# m2_feather_interposer.net
KiCad netlist of a schematic drawn in EAGLE
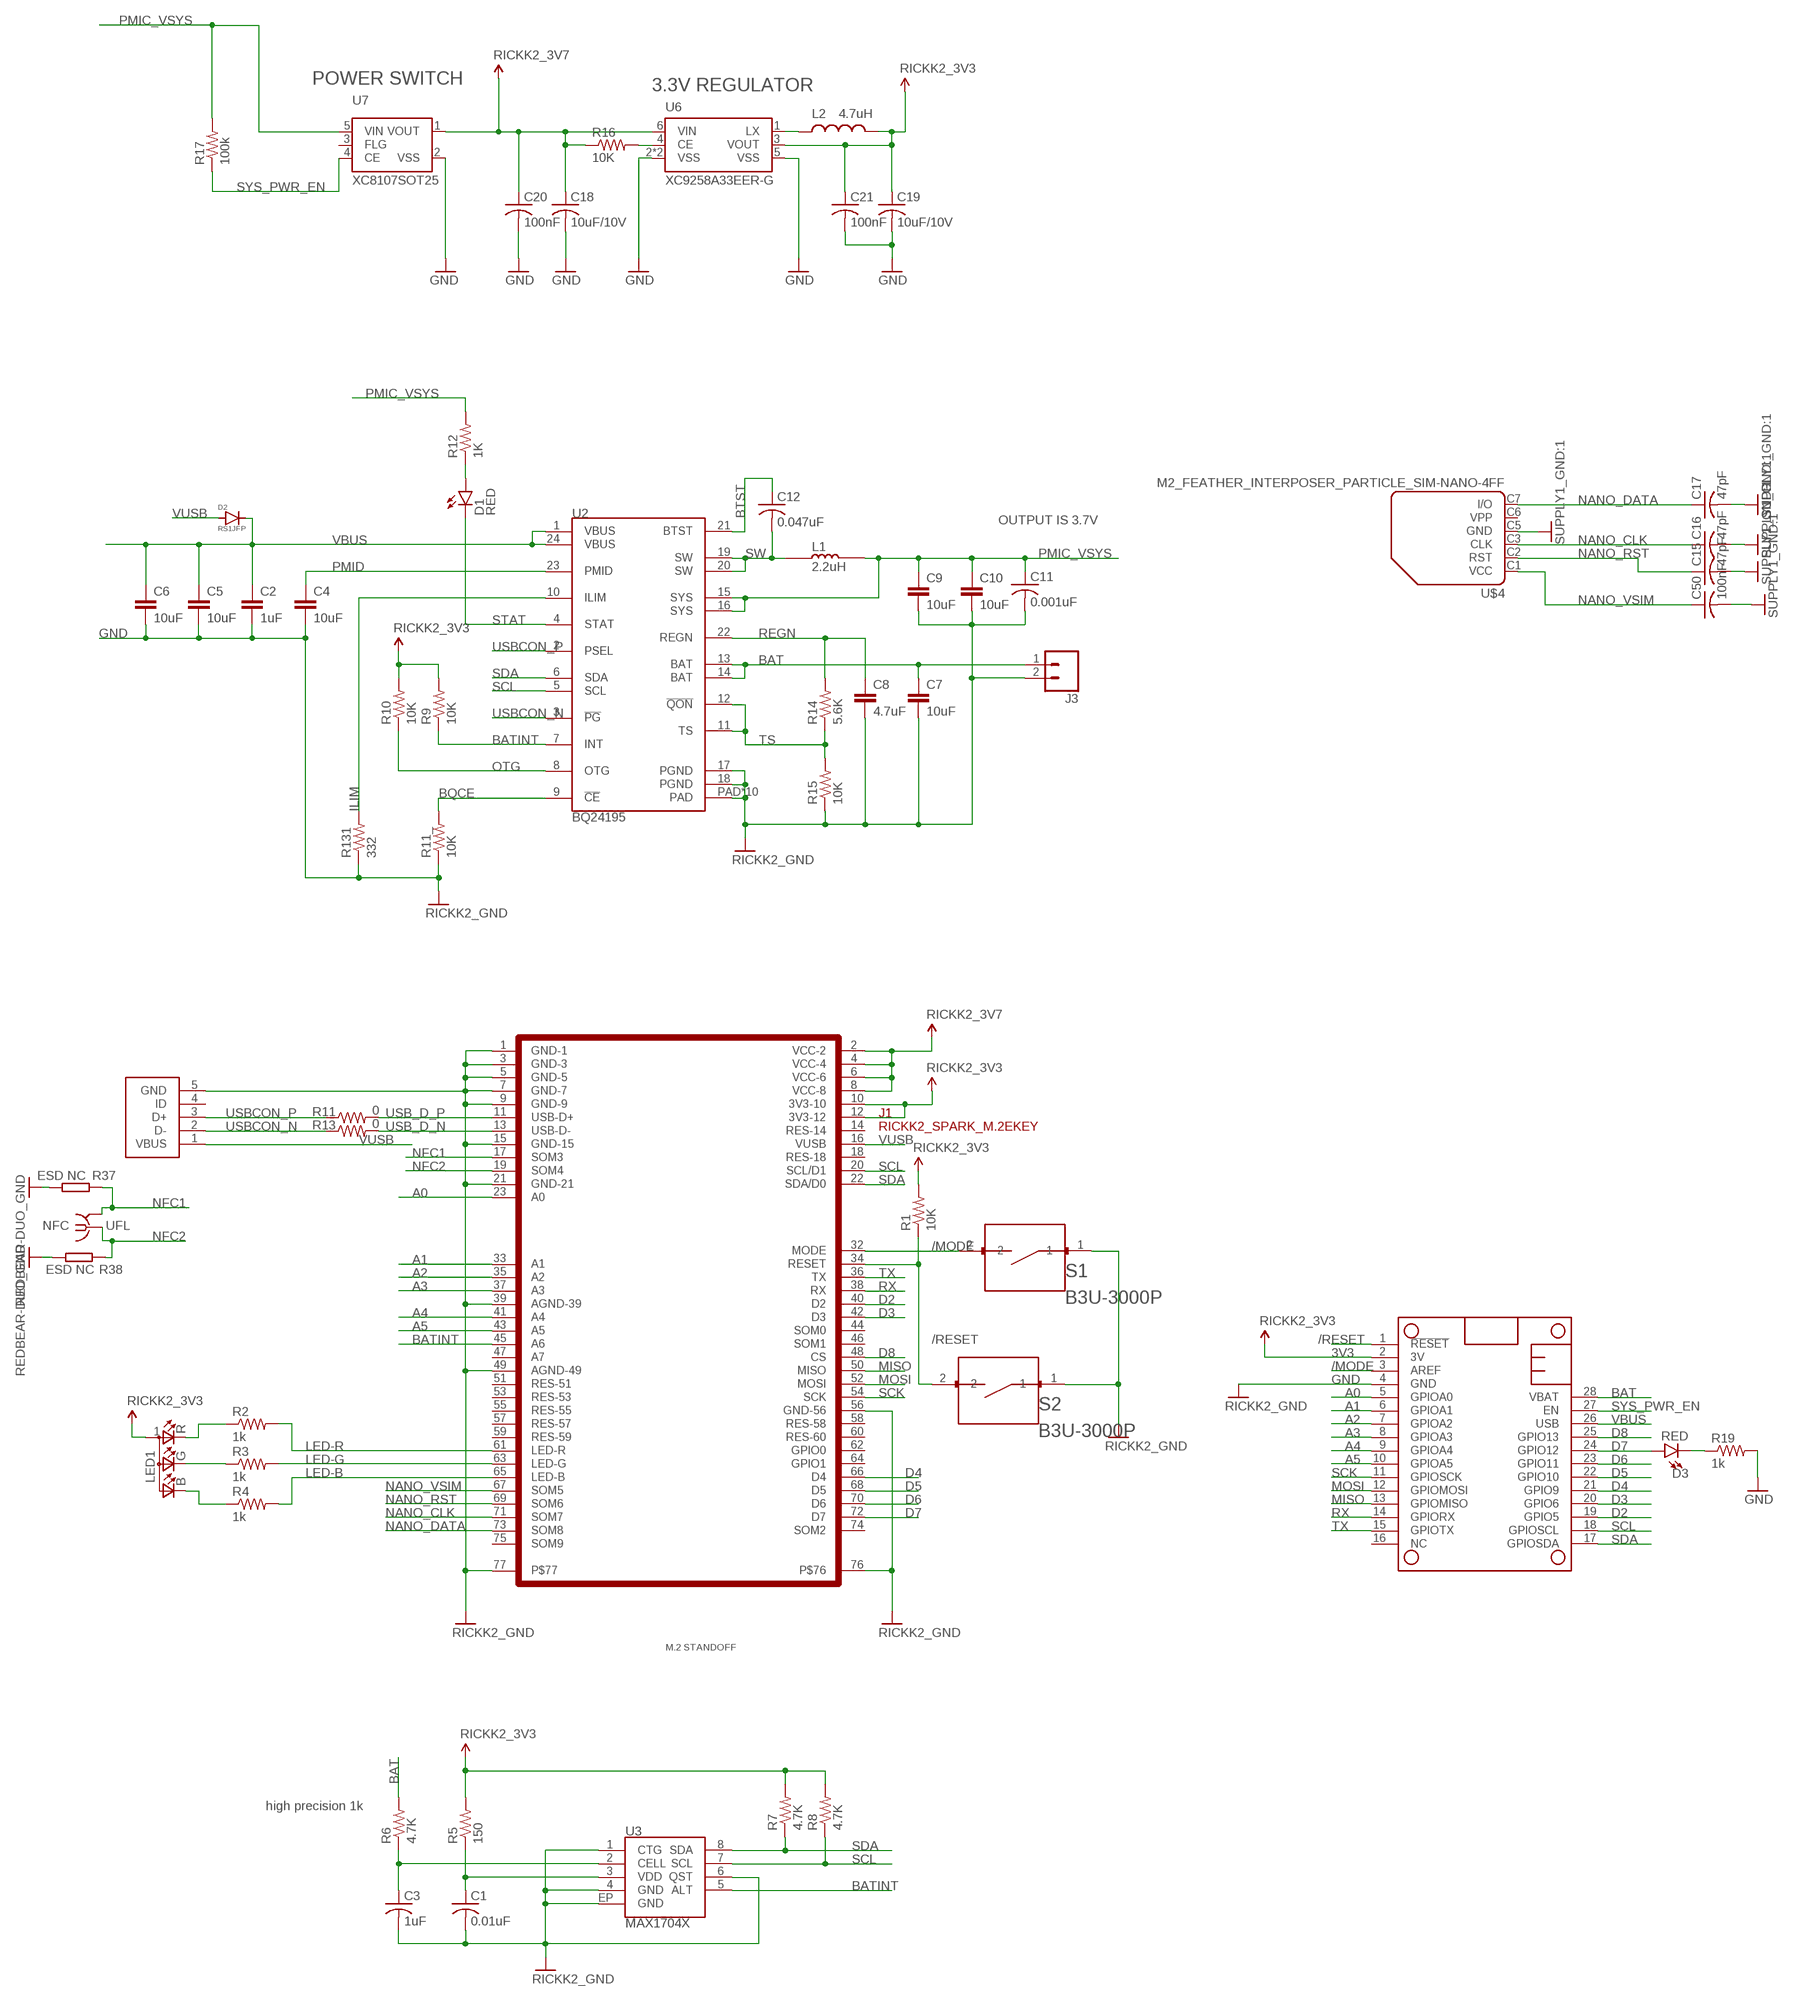
[diagram p0: schematic, sheet 1]

(export (version "E")
  (design (tool "Eeschema 10.0.6"))
  (components
    (comp (ref "C1")
      (value "0.01uF")
      (footprint "eagle-import:C0402")
      (libsource (lib "eagle-import") (part "C-USC0402"))
    )
    (comp (ref "C2")
      (value "1uF")
      (footprint "eagle-import:0603-CAP")
      (libsource (lib "eagle-import") (part "CAP-1UF-0603.DEV"))
    )
    (comp (ref "C3")
      (value "1uF")
      (footprint "eagle-import:C0402")
      (libsource (lib "eagle-import") (part "C-USC0402"))
    )
    (comp (ref "C4")
      (value "10uF")
      (footprint "eagle-import:RICKK2_0603-CAP")
      (libsource (lib "eagle-import") (part "RICKK2_CAP-10UF-0603"))
    )
    (comp (ref "C5")
      (value "10uF")
      (footprint "eagle-import:RICKK2_0603-CAP")
      (libsource (lib "eagle-import") (part "RICKK2_CAP-10UF-0603"))
    )
    (comp (ref "C6")
      (value "10uF")
      (footprint "eagle-import:RICKK2_0603-CAP")
      (libsource (lib "eagle-import") (part "RICKK2_CAP-10UF-0603"))
    )
    (comp (ref "C7")
      (value "10uF")
      (footprint "eagle-import:RICKK2_0603-CAP")
      (libsource (lib "eagle-import") (part "RICKK2_CAP-10UF-0603"))
    )
    (comp (ref "C8")
      (value "4.7uF")
      (footprint "eagle-import:RICKK2_0603-CAP")
      (libsource (lib "eagle-import") (part "RICKK2_CAP-4.7UF-0603"))
    )
    (comp (ref "C9")
      (value "10uF")
      (footprint "eagle-import:RICKK2_0603-CAP")
      (libsource (lib "eagle-import") (part "RICKK2_CAP-10UF-0603"))
    )
    (comp (ref "C10")
      (value "10uF")
      (footprint "eagle-import:RICKK2_0603-CAP")
      (libsource (lib "eagle-import") (part "RICKK2_CAP-10UF-0603"))
    )
    (comp (ref "C11")
      (value "0.001uF")
      (footprint "eagle-import:C0402")
      (libsource (lib "eagle-import") (part "C-USC0402"))
    )
    (comp (ref "C12")
      (value "0.047uF")
      (footprint "eagle-import:C0402")
      (libsource (lib "eagle-import") (part "C-USC0402"))
    )
    (comp (ref "C15")
      (value "47pF")
      (footprint "eagle-import:PARTICLE_C0201_B")
      (libsource (lib "eagle-import") (part "PARTICLE_C-USC0201_B"))
    )
    (comp (ref "C16")
      (value "47pF")
      (footprint "eagle-import:PARTICLE_C0201_B")
      (libsource (lib "eagle-import") (part "PARTICLE_C-USC0201_B"))
    )
    (comp (ref "C17")
      (value "47pF")
      (footprint "eagle-import:PARTICLE_C0201_B")
      (libsource (lib "eagle-import") (part "PARTICLE_C-USC0201_B"))
    )
    (comp (ref "C18")
      (value "10uF/10V")
      (footprint "eagle-import:C0603K")
      (libsource (lib "eagle-import") (part "rcl_334_C-USC0603K"))
    )
    (comp (ref "C19")
      (value "10uF/10V")
      (footprint "eagle-import:C0603K")
      (libsource (lib "eagle-import") (part "rcl_334_C-USC0603K"))
    )
    (comp (ref "C20")
      (value "100nF")
      (footprint "eagle-import:C0603K")
      (libsource (lib "eagle-import") (part "rcl_334_C-USC0603K"))
    )
    (comp (ref "C21")
      (value "100nF")
      (footprint "eagle-import:C0201_B")
      (libsource (lib "eagle-import") (part "C-USC0201_B"))
    )
    (comp (ref "C50")
      (value "100nF")
      (footprint "eagle-import:PARTICLE_C0201_B")
      (libsource (lib "eagle-import") (part "PARTICLE_C-USC0201_B"))
    )
    (comp (ref "D1")
      (value "RED")
      (footprint "eagle-import:RICKK2_LED-0603")
      (libsource (lib "eagle-import") (part "RICKK2_LED-RED"))
    )
    (comp (ref "D2")
      (value "RS1JFP")
      (footprint "eagle-import:RICKK2_SOD-123HE-ON")
      (libsource (lib "eagle-import") (part "RICKK2_DIODE-RS1JFP"))
    )
    (comp (ref "D3")
      (value "RED")
      (footprint "eagle-import:LED-0603")
      (libsource (lib "eagle-import") (part "LED-RED0603"))
    )
    (comp (ref "J1")
      (value "RICKK2_SPARK_M.2EKEY")
      (footprint "eagle-import:RICKK2_SPARK_M.2EKEY-LESS-CREAM")
      (libsource (lib "eagle-import") (part "RICKK2_SPARK_M.2EKEY"))
    )
    (comp (ref "J3")
      (value "CONN_02")
      (footprint "eagle-import:1X02")
      (libsource (lib "eagle-import") (part "CONN_02"))
    )
    (comp (ref "L1")
      (value "2.2uH")
      (footprint "eagle-import:RICKK2_1008-BOURNS")
      (libsource (lib "eagle-import") (part "RICKK2_INDUCTOR-2.2UH"))
    )
    (comp (ref "L2")
      (value "4.7uH")
      (footprint "eagle-import:INDUCTOR-VLS-E")
      (libsource (lib "eagle-import") (part "INDUCTOR-SPARKFUNVLS3012ET-4R7M"))
    )
    (comp (ref "LED1")
      (value "RICKK2_LED-RGB-CREE-SMD")
      (footprint "eagle-import:RICKK2_LED-RGB-CREE-SMD")
      (libsource (lib "eagle-import") (part "RICKK2_LED-RGB-CREE-SMD"))
    )
    (comp (ref "MS1")
      (value "MICROBUILDER_FEATHERWINGSMT_BTM_FEATHER")
      (footprint "eagle-import:SMT_BTM_FEATHERWING")
      (libsource (lib "eagle-import") (part "MICROBUILDER_FEATHERWINGSMT_BTM_FEATHER"))
    )
    (comp (ref "NFC")
      (value "UFL")
      (footprint "eagle-import:PARTICLE_IPEX-20279-001E")
      (libsource (lib "eagle-import") (part "PARTICLE_IPEX-20279-001E"))
    )
    (comp (ref "R1")
      (value "10K")
      (footprint "eagle-import:R0402")
      (libsource (lib "eagle-import") (part "R-US_R0402"))
    )
    (comp (ref "R2")
      (value "1k")
      (footprint "eagle-import:R0402")
      (libsource (lib "eagle-import") (part "R-US_R0402"))
    )
    (comp (ref "R3")
      (value "1k")
      (footprint "eagle-import:R0402")
      (libsource (lib "eagle-import") (part "R-US_R0402"))
    )
    (comp (ref "R4")
      (value "1k")
      (footprint "eagle-import:R0402")
      (libsource (lib "eagle-import") (part "R-US_R0402"))
    )
    (comp (ref "R5")
      (value "150")
      (footprint "eagle-import:R0402")
      (libsource (lib "eagle-import") (part "R-US_R0402"))
    )
    (comp (ref "R6")
      (value "4.7K")
      (footprint "eagle-import:R0402")
      (libsource (lib "eagle-import") (part "R-US_R0402"))
    )
    (comp (ref "R7")
      (value "4.7K")
      (footprint "eagle-import:R0402")
      (libsource (lib "eagle-import") (part "R-US_R0402"))
    )
    (comp (ref "R8")
      (value "4.7K")
      (footprint "eagle-import:R0402")
      (libsource (lib "eagle-import") (part "R-US_R0402"))
    )
    (comp (ref "R9")
      (value "10K")
      (footprint "eagle-import:R0402")
      (libsource (lib "eagle-import") (part "R-US_R0402"))
    )
    (comp (ref "R10")
      (value "10K")
      (footprint "eagle-import:R0402")
      (libsource (lib "eagle-import") (part "R-US_R0402"))
    )
    (comp (ref "R11")
      (value "0")
      (footprint "eagle-import:R0402")
      (libsource (lib "eagle-import") (part "R-US_R0402"))
    )
    (comp (ref "R11_")
      (value "10K")
      (footprint "eagle-import:R0402")
      (libsource (lib "eagle-import") (part "R-US_R0402"))
    )
    (comp (ref "R12")
      (value "1K")
      (footprint "eagle-import:R0402")
      (libsource (lib "eagle-import") (part "R-US_R0402"))
    )
    (comp (ref "R13")
      (value "0")
      (footprint "eagle-import:R0402")
      (libsource (lib "eagle-import") (part "R-US_R0402"))
    )
    (comp (ref "R14")
      (value "5.6K")
      (footprint "eagle-import:R0402")
      (libsource (lib "eagle-import") (part "R-US_R0402"))
    )
    (comp (ref "R15")
      (value "10K")
      (footprint "eagle-import:R0402")
      (libsource (lib "eagle-import") (part "R-US_R0402"))
    )
    (comp (ref "R16")
      (value "10K")
      (footprint "eagle-import:R0402")
      (libsource (lib "eagle-import") (part "R-US_R0402"))
    )
    (comp (ref "R17")
      (value "100k")
      (footprint "eagle-import:R0402")
      (libsource (lib "eagle-import") (part "R-US_R0402"))
    )
    (comp (ref "R19")
      (value "1k")
      (footprint "eagle-import:R0402")
      (libsource (lib "eagle-import") (part "R-US_R0402"))
    )
    (comp (ref "R37")
      (value "ESD NC")
      (footprint "eagle-import:REDBEAR_R-0402S")
      (libsource (lib "eagle-import") (part "REDBEAR_RES0402S"))
    )
    (comp (ref "R38")
      (value "ESD NC")
      (footprint "eagle-import:REDBEAR_R-0402S")
      (libsource (lib "eagle-import") (part "REDBEAR_RES0402S"))
    )
    (comp (ref "R131")
      (value "332")
      (footprint "eagle-import:R0402")
      (libsource (lib "eagle-import") (part "R-US_R0402"))
    )
    (comp (ref "S1")
      (value "B3U-3000P")
      (footprint "eagle-import:SW_B3U-3000P")
      (fields (field (name "MF") "Omron") (field (name "MP") "B3U-3100P-B"))
      (libsource (lib "eagle-import") (part "B3U-3000P"))
    )
    (comp (ref "S2")
      (value "B3U-3000P")
      (footprint "eagle-import:SW_B3U-3000P")
      (fields (field (name "MF") "Omron") (field (name "MP") "B3U-3100P-B"))
      (libsource (lib "eagle-import") (part "B3U-3000P"))
    )
    (comp (ref "U$1")
      (value "RICKK2_M2-STANDOFF")
      (footprint "eagle-import:RICKK2_M2-STANDOFF")
      (libsource (lib "eagle-import") (part "RICKK2_M2-STANDOFF"))
    )
    (comp (ref "U$3")
      (value "RICKK2_USB-MICRO-B-SOCKET-AMPHENOL")
      (footprint "eagle-import:RICKK2_USB-B-SMT-AMPHENOL")
      (libsource (lib "eagle-import") (part "RICKK2_USB-MICRO-B-SOCKET-AMPHENOL"))
    )
    (comp (ref "U$4")
      (value "M2_FEATHER_INTERPOSER_PARTICLE_SIM-NANO-4FF")
      (footprint "eagle-import:M2_FEATHER_INTERPOSER_PARTICLE_GCT-SIM8100")
      (libsource (lib "eagle-import") (part "M2_FEATHER_INTERPOSER_PARTICLE_SIM-NANO-4FF"))
    )
    (comp (ref "U2")
      (value "BQ24195")
      (footprint "eagle-import:RICKK2_24VFQN-TI")
      (libsource (lib "eagle-import") (part "RICKK2_BQ24195"))
    )
    (comp (ref "U3")
      (value "MAX1704X")
      (footprint "eagle-import:TDFN-8")
      (libsource (lib "eagle-import") (part "MAX1704X"))
    )
    (comp (ref "U6")
      (value "XC9258A33EER-G")
      (footprint "eagle-import:USP-6C")
      (libsource (lib "eagle-import") (part "XC9258A33EER-G"))
    )
    (comp (ref "U7")
      (value "XC8107SOT25")
      (footprint "eagle-import:SOT25")
      (libsource (lib "eagle-import") (part "XC8107SOT25"))
    )
  )
  (nets
    (net (code "1") (name "/A0") (class "Default")
      (node (ref "J1") (pin "23") (pinfunction "A0_23") (pintype "bidirectional"))
      (node (ref "MS1") (pin "5") (pinfunction "GPIOA0_5") (pintype "bidirectional"))
    )
    (net (code "2") (name "/A1") (class "Default")
      (node (ref "J1") (pin "33") (pinfunction "A1_33") (pintype "bidirectional"))
      (node (ref "MS1") (pin "6") (pinfunction "GPIOA1_6") (pintype "bidirectional"))
    )
    (net (code "3") (name "/A2") (class "Default")
      (node (ref "J1") (pin "35") (pinfunction "A2_35") (pintype "bidirectional"))
      (node (ref "MS1") (pin "7") (pinfunction "GPIOA2_7") (pintype "bidirectional"))
    )
    (net (code "4") (name "/A3") (class "Default")
      (node (ref "J1") (pin "37") (pinfunction "A3_37") (pintype "bidirectional"))
      (node (ref "MS1") (pin "8") (pinfunction "GPIOA3_8") (pintype "bidirectional"))
    )
    (net (code "5") (name "/A4") (class "Default")
      (node (ref "J1") (pin "41") (pinfunction "A4_41") (pintype "bidirectional"))
      (node (ref "MS1") (pin "9") (pinfunction "GPIOA4_9") (pintype "bidirectional"))
    )
    (net (code "6") (name "/A5") (class "Default")
      (node (ref "J1") (pin "43") (pinfunction "A5_43") (pintype "bidirectional"))
      (node (ref "MS1") (pin "10") (pinfunction "GPIOA5_10") (pintype "bidirectional"))
    )
    (net (code "7") (name "/BAT") (class "Default")
      (node (ref "C7") (pin "1") (pinfunction "1_1") (pintype "passive"))
      (node (ref "J3") (pin "1") (pinfunction "1_1") (pintype "passive"))
      (node (ref "MS1") (pin "28") (pinfunction "VBAT_28") (pintype "power_in"))
      (node (ref "R6") (pin "2") (pinfunction "2_2") (pintype "passive"))
      (node (ref "U2") (pin "13") (pinfunction "BAT_13") (pintype "passive"))
      (node (ref "U2") (pin "14") (pinfunction "BAT_14") (pintype "power_in"))
    )
    (net (code "8") (name "/BATINT") (class "Default")
      (node (ref "J1") (pin "45") (pinfunction "A6_45") (pintype "bidirectional"))
      (node (ref "R9") (pin "1") (pinfunction "1_1") (pintype "passive"))
      (node (ref "U2") (pin "7") (pinfunction "INT_7") (pintype "bidirectional"))
      (node (ref "U3") (pin "5") (pinfunction "ALT_5") (pintype "bidirectional"))
    )
    (net (code "9") (name "/BQCE") (class "Default")
      (node (ref "R11_") (pin "2") (pinfunction "2_2") (pintype "passive"))
      (node (ref "U2") (pin "9") (pinfunction "~{CE}_9") (pintype "output"))
    )
    (net (code "10") (name "/BTST") (class "Default")
      (node (ref "C12") (pin "1") (pinfunction "1_1") (pintype "passive"))
      (node (ref "U2") (pin "21") (pinfunction "BTST_21") (pintype "bidirectional"))
    )
    (net (code "11") (name "/D2") (class "Default")
      (node (ref "J1") (pin "40") (pinfunction "D2_40") (pintype "bidirectional"))
      (node (ref "MS1") (pin "19") (pinfunction "GPIO5_19") (pintype "bidirectional"))
    )
    (net (code "12") (name "/D3") (class "Default")
      (node (ref "J1") (pin "42") (pinfunction "D3_42") (pintype "bidirectional"))
      (node (ref "MS1") (pin "20") (pinfunction "GPIO6_20") (pintype "bidirectional"))
    )
    (net (code "13") (name "/D4") (class "Default")
      (node (ref "J1") (pin "66") (pinfunction "D4_66") (pintype "bidirectional"))
      (node (ref "MS1") (pin "21") (pinfunction "GPIO9_21") (pintype "bidirectional"))
    )
    (net (code "14") (name "/D5") (class "Default")
      (node (ref "J1") (pin "68") (pinfunction "D5_68") (pintype "bidirectional"))
      (node (ref "MS1") (pin "22") (pinfunction "GPIO10_22") (pintype "bidirectional"))
    )
    (net (code "15") (name "/D6") (class "Default")
      (node (ref "J1") (pin "70") (pinfunction "D6_70") (pintype "bidirectional"))
      (node (ref "MS1") (pin "23") (pinfunction "GPIO11_23") (pintype "bidirectional"))
    )
    (net (code "16") (name "/D7") (class "Default")
      (node (ref "D3") (pin "A") (pinfunction "A_A") (pintype "passive"))
      (node (ref "J1") (pin "72") (pinfunction "D7_72") (pintype "bidirectional"))
      (node (ref "MS1") (pin "24") (pinfunction "GPIO12_24") (pintype "bidirectional"))
    )
    (net (code "17") (name "/D8") (class "Default")
      (node (ref "J1") (pin "48") (pinfunction "CS_48") (pintype "bidirectional"))
      (node (ref "MS1") (pin "25") (pinfunction "GPIO13_25") (pintype "bidirectional"))
    )
    (net (code "18") (name "/ILIM") (class "Default")
      (node (ref "R131") (pin "2") (pinfunction "2_2") (pintype "passive"))
      (node (ref "U2") (pin "10") (pinfunction "ILIM_10") (pintype "output"))
    )
    (net (code "19") (name "/LED-B") (class "Default")
      (node (ref "J1") (pin "65") (pinfunction "LED-B_65") (pintype "bidirectional"))
      (node (ref "R4") (pin "2") (pinfunction "2_2") (pintype "passive"))
    )
    (net (code "20") (name "/LED-G") (class "Default")
      (node (ref "J1") (pin "63") (pinfunction "LED-G_63") (pintype "bidirectional"))
      (node (ref "R3") (pin "2") (pinfunction "2_2") (pintype "passive"))
    )
    (net (code "21") (name "/LED-R") (class "Default")
      (node (ref "J1") (pin "61") (pinfunction "LED-R_61") (pintype "bidirectional"))
      (node (ref "R2") (pin "2") (pinfunction "2_2") (pintype "passive"))
    )
    (net (code "22") (name "/MISO") (class "Default")
      (node (ref "J1") (pin "50") (pinfunction "MISO_50") (pintype "bidirectional"))
      (node (ref "MS1") (pin "13") (pinfunction "GPIOMISO_13") (pintype "bidirectional"))
    )
    (net (code "23") (name "/MOSI") (class "Default")
      (node (ref "J1") (pin "52") (pinfunction "MOSI_52") (pintype "bidirectional"))
      (node (ref "MS1") (pin "12") (pinfunction "GPIOMOSI_12") (pintype "bidirectional"))
    )
    (net (code "24") (name "/NANO_CLK") (class "Default")
      (node (ref "C16") (pin "1") (pinfunction "1_1") (pintype "passive"))
      (node (ref "J1") (pin "71") (pinfunction "SOM7_71") (pintype "bidirectional"))
      (node (ref "U$4") (pin "C3") (pinfunction "CLK_C3") (pintype "passive"))
    )
    (net (code "25") (name "/NANO_DATA") (class "Default")
      (node (ref "C17") (pin "1") (pinfunction "1_1") (pintype "passive"))
      (node (ref "J1") (pin "73") (pinfunction "SOM8_73") (pintype "bidirectional"))
      (node (ref "U$4") (pin "C7") (pinfunction "I/O_C7") (pintype "passive"))
    )
    (net (code "26") (name "/NANO_RST") (class "Default")
      (node (ref "C15") (pin "1") (pinfunction "1_1") (pintype "passive"))
      (node (ref "J1") (pin "69") (pinfunction "SOM6_69") (pintype "bidirectional"))
      (node (ref "U$4") (pin "C2") (pinfunction "RST_C2") (pintype "passive"))
    )
    (net (code "27") (name "/NANO_VSIM") (class "Default")
      (node (ref "C50") (pin "1") (pinfunction "1_1") (pintype "passive"))
      (node (ref "J1") (pin "67") (pinfunction "SOM5_67") (pintype "bidirectional"))
      (node (ref "U$4") (pin "C1") (pinfunction "VCC_C1") (pintype "passive"))
    )
    (net (code "28") (name "/NFC1") (class "Default")
      (node (ref "J1") (pin "17") (pinfunction "SOM3_17") (pintype "bidirectional"))
      (node (ref "NFC") (pin "2@1") (pinfunction "GND_2@1") (pintype "passive"))
      (node (ref "NFC") (pin "2@2") (pinfunction "GND_2@2") (pintype "passive"))
      (node (ref "R37") (pin "1") (pinfunction "1_1") (pintype "bidirectional"))
    )
    (net (code "29") (name "/NFC2") (class "Default")
      (node (ref "J1") (pin "19") (pinfunction "SOM4_19") (pintype "bidirectional"))
      (node (ref "NFC") (pin "1") (pinfunction "1_1") (pintype "passive"))
      (node (ref "R38") (pin "2") (pinfunction "2_2") (pintype "bidirectional"))
    )
    (net (code "30") (name "/OTG") (class "Default")
      (node (ref "R10") (pin "1") (pinfunction "1_1") (pintype "passive"))
      (node (ref "U2") (pin "8") (pinfunction "OTG_8") (pintype "bidirectional"))
    )
    (net (code "31") (name "/PMIC_VSYS") (class "Default")
      (node (ref "C10") (pin "1") (pinfunction "1_1") (pintype "passive"))
      (node (ref "C11") (pin "1") (pinfunction "1_1") (pintype "passive"))
      (node (ref "C9") (pin "1") (pinfunction "1_1") (pintype "passive"))
      (node (ref "L1") (pin "2") (pinfunction "P$2_2") (pintype "passive"))
      (node (ref "R12") (pin "2") (pinfunction "2_2") (pintype "passive"))
      (node (ref "R17") (pin "2") (pinfunction "2_2") (pintype "passive"))
      (node (ref "U2") (pin "15") (pinfunction "SYS_15") (pintype "power_in"))
      (node (ref "U2") (pin "16") (pinfunction "SYS_16") (pintype "power_in"))
      (node (ref "U7") (pin "5") (pinfunction "VIN_5") (pintype "power_in"))
    )
    (net (code "32") (name "/PMID") (class "Default")
      (node (ref "C4") (pin "1") (pinfunction "1_1") (pintype "passive"))
      (node (ref "U2") (pin "23") (pinfunction "PMID_23") (pintype "passive"))
    )
    (net (code "33") (name "/REGN") (class "Default")
      (node (ref "C8") (pin "1") (pinfunction "1_1") (pintype "passive"))
      (node (ref "R14") (pin "2") (pinfunction "2_2") (pintype "passive"))
      (node (ref "U2") (pin "22") (pinfunction "REGN_22") (pintype "bidirectional"))
    )
    (net (code "34") (name "/RX") (class "Default")
      (node (ref "J1") (pin "38") (pinfunction "RX_38") (pintype "bidirectional"))
      (node (ref "MS1") (pin "14") (pinfunction "GPIORX_14") (pintype "bidirectional"))
    )
    (net (code "35") (name "/SCK") (class "Default")
      (node (ref "J1") (pin "54") (pinfunction "SCK_54") (pintype "bidirectional"))
      (node (ref "MS1") (pin "11") (pinfunction "GPIOSCK_11") (pintype "bidirectional"))
    )
    (net (code "36") (name "/SCL") (class "Default")
      (node (ref "J1") (pin "20") (pinfunction "SCL/D1_20") (pintype "bidirectional"))
      (node (ref "MS1") (pin "18") (pinfunction "GPIOSCL_18") (pintype "bidirectional"))
      (node (ref "R8") (pin "1") (pinfunction "1_1") (pintype "passive"))
      (node (ref "U2") (pin "5") (pinfunction "SCL_5") (pintype "output"))
      (node (ref "U3") (pin "7") (pinfunction "SCL_7") (pintype "bidirectional"))
    )
    (net (code "37") (name "/SDA") (class "Default")
      (node (ref "J1") (pin "22") (pinfunction "SDA/D0_22") (pintype "bidirectional"))
      (node (ref "MS1") (pin "17") (pinfunction "GPIOSDA_17") (pintype "bidirectional"))
      (node (ref "R7") (pin "1") (pinfunction "1_1") (pintype "passive"))
      (node (ref "U2") (pin "6") (pinfunction "SDA_6") (pintype "bidirectional"))
      (node (ref "U3") (pin "8") (pinfunction "SDA_8") (pintype "bidirectional"))
    )
    (net (code "38") (name "/STAT") (class "Default")
      (node (ref "D1") (pin "C") (pinfunction "C_C") (pintype "passive"))
      (node (ref "U2") (pin "4") (pinfunction "STAT_4") (pintype "bidirectional"))
    )
    (net (code "39") (name "/SW") (class "Default")
      (node (ref "C12") (pin "2") (pinfunction "2_2") (pintype "passive"))
      (node (ref "L1") (pin "1") (pinfunction "P$1_1") (pintype "passive"))
      (node (ref "U2") (pin "19") (pinfunction "SW_19") (pintype "power_in"))
      (node (ref "U2") (pin "20") (pinfunction "SW_20") (pintype "power_in"))
    )
    (net (code "40") (name "/SYS_PWR_EN") (class "Default")
      (node (ref "MS1") (pin "27") (pinfunction "EN_27") (pintype "passive"))
      (node (ref "R17") (pin "1") (pinfunction "1_1") (pintype "passive"))
      (node (ref "U7") (pin "4") (pinfunction "CE_4") (pintype "bidirectional"))
    )
    (net (code "41") (name "/TS") (class "Default")
      (node (ref "R14") (pin "1") (pinfunction "1_1") (pintype "passive"))
      (node (ref "R15") (pin "2") (pinfunction "2_2") (pintype "passive"))
      (node (ref "U2") (pin "11") (pinfunction "TS_11") (pintype "bidirectional"))
      (node (ref "U2") (pin "12") (pinfunction "~{QON}_12") (pintype "bidirectional"))
    )
    (net (code "42") (name "/TX") (class "Default")
      (node (ref "J1") (pin "36") (pinfunction "TX_36") (pintype "bidirectional"))
      (node (ref "MS1") (pin "15") (pinfunction "GPIOTX_15") (pintype "bidirectional"))
    )
    (net (code "43") (name "/USBCON_N") (class "Default")
      (node (ref "R13") (pin "1") (pinfunction "1_1") (pintype "passive"))
      (node (ref "U$3") (pin "2") (pinfunction "D-_2") (pintype "passive"))
      (node (ref "U2") (pin "3") (pinfunction "~{PG}_3") (pintype "output"))
    )
    (net (code "44") (name "/USBCON_P") (class "Default")
      (node (ref "R11") (pin "1") (pinfunction "1_1") (pintype "passive"))
      (node (ref "U$3") (pin "3") (pinfunction "D+_3") (pintype "passive"))
      (node (ref "U2") (pin "2") (pinfunction "PSEL_2") (pintype "output"))
    )
    (net (code "45") (name "/USB_D_N") (class "Default")
      (node (ref "J1") (pin "13") (pinfunction "USB-D-_13") (pintype "bidirectional"))
      (node (ref "R13") (pin "2") (pinfunction "2_2") (pintype "passive"))
    )
    (net (code "46") (name "/USB_D_P") (class "Default")
      (node (ref "J1") (pin "11") (pinfunction "USB-D+_11") (pintype "bidirectional"))
      (node (ref "R11") (pin "2") (pinfunction "2_2") (pintype "passive"))
    )
    (net (code "47") (name "/VBUS") (class "Default")
      (node (ref "C2") (pin "1") (pinfunction "1_1") (pintype "passive"))
      (node (ref "C5") (pin "1") (pinfunction "1_1") (pintype "passive"))
      (node (ref "C6") (pin "1") (pinfunction "1_1") (pintype "passive"))
      (node (ref "D2") (pin "1") (pinfunction "CATHODE_1") (pintype "bidirectional"))
      (node (ref "MS1") (pin "26") (pinfunction "USB_26") (pintype "power_in"))
      (node (ref "U2") (pin "1") (pinfunction "VBUS_1") (pintype "power_in"))
      (node (ref "U2") (pin "24") (pinfunction "VBUS_24") (pintype "passive"))
    )
    (net (code "48") (name "/VUSB") (class "Default")
      (node (ref "D2") (pin "2") (pinfunction "ANODE_2") (pintype "bidirectional"))
      (node (ref "J1") (pin "16") (pinfunction "VUSB_16") (pintype "bidirectional"))
      (node (ref "U$3") (pin "1") (pinfunction "VBUS_1") (pintype "passive"))
    )
    (net (code "49") (name "/{slash}MODE") (class "Default")
      (node (ref "J1") (pin "32") (pinfunction "MODE_32") (pintype "bidirectional"))
      (node (ref "MS1") (pin "3") (pinfunction "AREF_3") (pintype "passive"))
      (node (ref "S1") (pin "2") (pinfunction "2_2") (pintype "passive"))
    )
    (net (code "50") (name "/{slash}RESET") (class "Default")
      (node (ref "J1") (pin "34") (pinfunction "RESET_34") (pintype "bidirectional"))
      (node (ref "MS1") (pin "1") (pinfunction "~{RESET}_1") (pintype "input"))
      (node (ref "R1") (pin "1") (pinfunction "1_1") (pintype "passive"))
      (node (ref "S2") (pin "2") (pinfunction "2_2") (pintype "passive"))
    )
    (net (code "51") (name "GND") (class "Default")
      (node (ref "C1") (pin "2") (pinfunction "2_2") (pintype "passive"))
      (node (ref "C10") (pin "2") (pinfunction "2_2") (pintype "passive"))
      (node (ref "C11") (pin "2") (pinfunction "2_2") (pintype "passive"))
      (node (ref "C15") (pin "2") (pinfunction "2_2") (pintype "passive"))
      (node (ref "C16") (pin "2") (pinfunction "2_2") (pintype "passive"))
      (node (ref "C17") (pin "2") (pinfunction "2_2") (pintype "passive"))
      (node (ref "C18") (pin "2") (pinfunction "2_2") (pintype "passive"))
      (node (ref "C19") (pin "2") (pinfunction "2_2") (pintype "passive"))
      (node (ref "C2") (pin "2") (pinfunction "2_2") (pintype "passive"))
      (node (ref "C20") (pin "2") (pinfunction "2_2") (pintype "passive"))
      (node (ref "C21") (pin "2") (pinfunction "2_2") (pintype "passive"))
      (node (ref "C3") (pin "2") (pinfunction "2_2") (pintype "passive"))
      (node (ref "C4") (pin "2") (pinfunction "2_2") (pintype "passive"))
      (node (ref "C5") (pin "2") (pinfunction "2_2") (pintype "passive"))
      (node (ref "C50") (pin "2") (pinfunction "2_2") (pintype "passive"))
      (node (ref "C6") (pin "2") (pinfunction "2_2") (pintype "passive"))
      (node (ref "C7") (pin "2") (pinfunction "2_2") (pintype "passive"))
      (node (ref "C8") (pin "2") (pinfunction "2_2") (pintype "passive"))
      (node (ref "C9") (pin "2") (pinfunction "2_2") (pintype "passive"))
      (node (ref "J1") (pin "1") (pinfunction "GND-1_1") (pintype "bidirectional"))
      (node (ref "J1") (pin "15") (pinfunction "GND-15_15") (pintype "bidirectional"))
      (node (ref "J1") (pin "21") (pinfunction "GND-21_21") (pintype "bidirectional"))
      (node (ref "J1") (pin "3") (pinfunction "GND-3_3") (pintype "bidirectional"))
      (node (ref "J1") (pin "39") (pinfunction "AGND-39_39") (pintype "bidirectional"))
      (node (ref "J1") (pin "49") (pinfunction "AGND-49_49") (pintype "bidirectional"))
      (node (ref "J1") (pin "5") (pinfunction "GND-5_5") (pintype "bidirectional"))
      (node (ref "J1") (pin "56") (pinfunction "GND-56_56") (pintype "bidirectional"))
      (node (ref "J1") (pin "7") (pinfunction "GND-7_7") (pintype "bidirectional"))
      (node (ref "J1") (pin "76") (pinfunction "P$76_76") (pintype "power_in"))
      (node (ref "J1") (pin "77") (pinfunction "P$77_77") (pintype "power_in"))
      (node (ref "J1") (pin "9") (pinfunction "GND-9_9") (pintype "bidirectional"))
      (node (ref "J3") (pin "2") (pinfunction "2_2") (pintype "passive"))
      (node (ref "MS1") (pin "4") (pinfunction "GND_4") (pintype "power_in"))
      (node (ref "R11_") (pin "1") (pinfunction "1_1") (pintype "passive"))
      (node (ref "R131") (pin "1") (pinfunction "1_1") (pintype "passive"))
      (node (ref "R15") (pin "1") (pinfunction "1_1") (pintype "passive"))
      (node (ref "R19") (pin "2") (pinfunction "2_2") (pintype "passive"))
      (node (ref "R37") (pin "2") (pinfunction "2_2") (pintype "bidirectional"))
      (node (ref "R38") (pin "1") (pinfunction "1_1") (pintype "bidirectional"))
      (node (ref "S1") (pin "1") (pinfunction "1_1") (pintype "passive"))
      (node (ref "S2") (pin "1") (pinfunction "1_1") (pintype "passive"))
      (node (ref "U$3") (pin "5") (pinfunction "GND_5") (pintype "passive"))
      (node (ref "U$4") (pin "C5") (pinfunction "GND_C5") (pintype "passive"))
      (node (ref "U2") (pin "17") (pinfunction "PGND_17") (pintype "passive"))
      (node (ref "U2") (pin "18") (pinfunction "PGND_18") (pintype "passive"))
      (node (ref "U2") (pin "PAD") (pinfunction "PAD_PAD") (pintype "power_in"))
      (node (ref "U2") (pin "PAD@1") (pinfunction "PAD_PAD@1") (pintype "power_in"))
      (node (ref "U2") (pin "PAD@2") (pinfunction "PAD_PAD@2") (pintype "power_in"))
      (node (ref "U2") (pin "PAD@3") (pinfunction "PAD_PAD@3") (pintype "power_in"))
      (node (ref "U2") (pin "PAD@4") (pinfunction "PAD_PAD@4") (pintype "power_in"))
      (node (ref "U2") (pin "PAD@5") (pinfunction "PAD_PAD@5") (pintype "power_in"))
      (node (ref "U2") (pin "PAD@6") (pinfunction "PAD_PAD@6") (pintype "power_in"))
      (node (ref "U2") (pin "PAD@7") (pinfunction "PAD_PAD@7") (pintype "power_in"))
      (node (ref "U2") (pin "PAD@8") (pinfunction "PAD_PAD@8") (pintype "power_in"))
      (node (ref "U2") (pin "PAD@9") (pinfunction "PAD_PAD@9") (pintype "power_in"))
      (node (ref "U3") (pin "1") (pinfunction "CTG_1") (pintype "bidirectional"))
      (node (ref "U3") (pin "4") (pinfunction "GND_4") (pintype "bidirectional"))
      (node (ref "U3") (pin "6") (pinfunction "QST_6") (pintype "bidirectional"))
      (node (ref "U3") (pin "EP") (pinfunction "GND_EP") (pintype "bidirectional"))
      (node (ref "U6") (pin "2") (pinfunction "VSS_2") (pintype "power_in"))
      (node (ref "U6") (pin "5") (pinfunction "VSS_5") (pintype "power_in"))
      (node (ref "U6") (pin "P$1") (pinfunction "VSS_P$1") (pintype "power_in"))
      (node (ref "U7") (pin "2") (pinfunction "VSS_2") (pintype "power_in"))
    )
    (net (code "52") (name "Net-(D1-PadA)") (class "Default")
      (node (ref "D1") (pin "A") (pinfunction "A_A") (pintype "passive"))
      (node (ref "R12") (pin "1") (pinfunction "1_1") (pintype "passive"))
    )
    (net (code "53") (name "Net-(D3-PadC)") (class "Default")
      (node (ref "D3") (pin "C") (pinfunction "C_C") (pintype "passive"))
      (node (ref "R19") (pin "1") (pinfunction "1_1") (pintype "passive"))
    )
    (net (code "54") (name "Net-(L2-1)") (class "Default")
      (node (ref "L2") (pin "P$1") (pinfunction "1_P$1") (pintype "passive"))
      (node (ref "U6") (pin "1") (pinfunction "LX_1") (pintype "bidirectional"))
    )
    (net (code "55") (name "Net-(LED1-B)") (class "Default")
      (node (ref "LED1") (pin "2") (pinfunction "B_2") (pintype "passive"))
      (node (ref "R4") (pin "1") (pinfunction "1_1") (pintype "passive"))
    )
    (net (code "56") (name "Net-(LED1-G)") (class "Default")
      (node (ref "LED1") (pin "3") (pinfunction "G_3") (pintype "passive"))
      (node (ref "R3") (pin "1") (pinfunction "1_1") (pintype "passive"))
    )
    (net (code "57") (name "Net-(LED1-R)") (class "Default")
      (node (ref "LED1") (pin "4") (pinfunction "R_4") (pintype "passive"))
      (node (ref "R2") (pin "1") (pinfunction "1_1") (pintype "passive"))
    )
    (net (code "58") (name "Net-(U3-CELL)") (class "Default")
      (node (ref "C3") (pin "1") (pinfunction "1_1") (pintype "passive"))
      (node (ref "R6") (pin "1") (pinfunction "1_1") (pintype "passive"))
      (node (ref "U3") (pin "2") (pinfunction "CELL_2") (pintype "bidirectional"))
    )
    (net (code "59") (name "Net-(U3-VDD)") (class "Default")
      (node (ref "C1") (pin "1") (pinfunction "1_1") (pintype "passive"))
      (node (ref "R5") (pin "1") (pinfunction "1_1") (pintype "passive"))
      (node (ref "U3") (pin "3") (pinfunction "VDD_3") (pintype "bidirectional"))
    )
    (net (code "60") (name "Net-(U6-CE)") (class "Default")
      (node (ref "R16") (pin "2") (pinfunction "2_2") (pintype "passive"))
      (node (ref "U6") (pin "4") (pinfunction "CE_4") (pintype "bidirectional"))
    )
    (net (code "61") (name "RICKK2_3V3") (class "Default")
      (node (ref "C19") (pin "1") (pinfunction "1_1") (pintype "passive"))
      (node (ref "C21") (pin "1") (pinfunction "1_1") (pintype "passive"))
      (node (ref "J1") (pin "10") (pinfunction "3V3-10_10") (pintype "bidirectional"))
      (node (ref "J1") (pin "12") (pinfunction "3V3-12_12") (pintype "bidirectional"))
      (node (ref "L2") (pin "P$2") (pinfunction "2_P$2") (pintype "passive"))
      (node (ref "LED1") (pin "1") (pinfunction "A_1") (pintype "passive"))
      (node (ref "MS1") (pin "2") (pinfunction "3V_2") (pintype "power_in"))
      (node (ref "R1") (pin "2") (pinfunction "2_2") (pintype "passive"))
      (node (ref "R10") (pin "2") (pinfunction "2_2") (pintype "passive"))
      (node (ref "R5") (pin "2") (pinfunction "2_2") (pintype "passive"))
      (node (ref "R7") (pin "2") (pinfunction "2_2") (pintype "passive"))
      (node (ref "R8") (pin "2") (pinfunction "2_2") (pintype "passive"))
      (node (ref "R9") (pin "2") (pinfunction "2_2") (pintype "passive"))
      (node (ref "U6") (pin "3") (pinfunction "VOUT_3") (pintype "power_in"))
    )
    (net (code "62") (name "RICKK2_3V7") (class "Default")
      (node (ref "C18") (pin "1") (pinfunction "1_1") (pintype "passive"))
      (node (ref "C20") (pin "1") (pinfunction "1_1") (pintype "passive"))
      (node (ref "J1") (pin "2") (pinfunction "VCC-2_2") (pintype "bidirectional"))
      (node (ref "J1") (pin "4") (pinfunction "VCC-4_4") (pintype "bidirectional"))
      (node (ref "J1") (pin "6") (pinfunction "VCC-6_6") (pintype "bidirectional"))
      (node (ref "J1") (pin "8") (pinfunction "VCC-8_8") (pintype "bidirectional"))
      (node (ref "R16") (pin "1") (pinfunction "1_1") (pintype "passive"))
      (node (ref "U6") (pin "6") (pinfunction "VIN_6") (pintype "power_in"))
      (node (ref "U7") (pin "1") (pinfunction "VOUT_1") (pintype "power_in"))
    )
    (net (code "63") (name "unconnected-(J1-A7-Pad47)") (class "Default")
      (node (ref "J1") (pin "47") (pinfunction "A7_47") (pintype "bidirectional"))
    )
    (net (code "64") (name "unconnected-(J1-GPIO0-Pad62)") (class "Default")
      (node (ref "J1") (pin "62") (pinfunction "GPIO0_62") (pintype "bidirectional"))
    )
    (net (code "65") (name "unconnected-(J1-GPIO1-Pad64)") (class "Default")
      (node (ref "J1") (pin "64") (pinfunction "GPIO1_64") (pintype "bidirectional"))
    )
    (net (code "66") (name "unconnected-(J1-RES-14-Pad14)") (class "Default")
      (node (ref "J1") (pin "14") (pinfunction "RES-14_14") (pintype "bidirectional"))
    )
    (net (code "67") (name "unconnected-(J1-RES-18-Pad18)") (class "Default")
      (node (ref "J1") (pin "18") (pinfunction "RES-18_18") (pintype "bidirectional"))
    )
    (net (code "68") (name "unconnected-(J1-RES-51-Pad51)") (class "Default")
      (node (ref "J1") (pin "51") (pinfunction "RES-51_51") (pintype "bidirectional"))
    )
    (net (code "69") (name "unconnected-(J1-RES-53-Pad53)") (class "Default")
      (node (ref "J1") (pin "53") (pinfunction "RES-53_53") (pintype "bidirectional"))
    )
    (net (code "70") (name "unconnected-(J1-RES-55-Pad55)") (class "Default")
      (node (ref "J1") (pin "55") (pinfunction "RES-55_55") (pintype "bidirectional"))
    )
    (net (code "71") (name "unconnected-(J1-RES-57-Pad57)") (class "Default")
      (node (ref "J1") (pin "57") (pinfunction "RES-57_57") (pintype "bidirectional"))
    )
    (net (code "72") (name "unconnected-(J1-RES-58-Pad58)") (class "Default")
      (node (ref "J1") (pin "58") (pinfunction "RES-58_58") (pintype "bidirectional"))
    )
    (net (code "73") (name "unconnected-(J1-RES-59-Pad59)") (class "Default")
      (node (ref "J1") (pin "59") (pinfunction "RES-59_59") (pintype "bidirectional"))
    )
    (net (code "74") (name "unconnected-(J1-RES-60-Pad60)") (class "Default")
      (node (ref "J1") (pin "60") (pinfunction "RES-60_60") (pintype "bidirectional"))
    )
    (net (code "75") (name "unconnected-(J1-SOM0-Pad44)") (class "Default")
      (node (ref "J1") (pin "44") (pinfunction "SOM0_44") (pintype "bidirectional"))
    )
    (net (code "76") (name "unconnected-(J1-SOM1-Pad46)") (class "Default")
      (node (ref "J1") (pin "46") (pinfunction "SOM1_46") (pintype "bidirectional"))
    )
    (net (code "77") (name "unconnected-(J1-SOM2-Pad74)") (class "Default")
      (node (ref "J1") (pin "74") (pinfunction "SOM2_74") (pintype "bidirectional"))
    )
    (net (code "78") (name "unconnected-(J1-SOM9-Pad75)") (class "Default")
      (node (ref "J1") (pin "75") (pinfunction "SOM9_75") (pintype "bidirectional"))
    )
    (net (code "79") (name "unconnected-(MS1-NC-Pad16)") (class "Default")
      (node (ref "MS1") (pin "16") (pinfunction "NC_16") (pintype "passive"))
    )
    (net (code "80") (name "unconnected-(U$3-ID-Pad4)") (class "Default")
      (node (ref "U$3") (pin "4") (pinfunction "ID_4") (pintype "passive"))
    )
    (net (code "81") (name "unconnected-(U$4-VPP-PadC6)") (class "Default")
      (node (ref "U$4") (pin "C6") (pinfunction "VPP_C6") (pintype "passive"))
    )
    (net (code "82") (name "unconnected-(U7-FLG-Pad3)") (class "Default")
      (node (ref "U7") (pin "3") (pinfunction "FLG_3") (pintype "bidirectional"))
    )
  )
)
